# Magnetic-Charger.net
KiCad netlist of a schematic drawn in Altium Designer
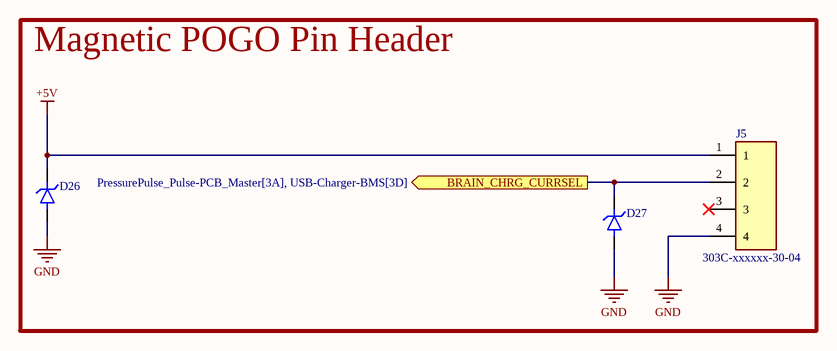
[diagram p0: Magnetic-Charger.SchDoc]

(export (version "E")
  (design (tool "Eeschema 10.0.6"))
  (components
    (comp (ref "D26")
      (value "RCLAMP0521P.TCT")
      (footprint "PressurePulse:BDFN2C051V40")
      (description "25V Clamp 4A (8/20µs) Ipp Tvs Diode Surface Mount SLP1006P2")
      (fields (field (name "MFR") "BORN"))
      (libsource (lib "PressurePulse") (part "TVS DIODE"))
    )
    (comp (ref "D27")
      (value "RCLAMP0521P.TCT")
      (footprint "PressurePulse:BDFN2C051V40")
      (description "25V Clamp 4A (8/20µs) Ipp Tvs Diode Surface Mount SLP1006P2")
      (fields (field (name "MFR") "BORN"))
      (libsource (lib "PressurePulse") (part "TVS DIODE"))
    )
    (comp (ref "J5")
      (value "303C-xxxxxx-30-04")
      (footprint "PressurePulse:MAG POGO - 4 POS MALE")
      (description "MAGNETIC POGO 4POS")
      (fields (field (name "MFR") "ATTEND Technology"))
      (libsource (lib "PressurePulse") (part "303C-xxxxxx-30-04"))
    )
  )
  (nets
    (net (code "1") (name "+5V") (class "Default")
      (node (ref "D26") (pin "K") (pinfunction "K_K") (pintype "passive"))
      (node (ref "J5") (pin "1") (pinfunction "1_1") (pintype "passive"))
    )
    (net (code "2") (name "/BRAIN_CHRG_CURRSEL") (class "Default")
      (node (ref "D27") (pin "K") (pinfunction "K_K") (pintype "passive"))
      (node (ref "J5") (pin "2") (pinfunction "2_2") (pintype "passive"))
    )
    (net (code "3") (name "GND") (class "Default")
      (node (ref "D26") (pin "A") (pinfunction "A_A") (pintype "passive"))
      (node (ref "D27") (pin "A") (pinfunction "A_A") (pintype "passive"))
      (node (ref "J5") (pin "4") (pinfunction "4_4") (pintype "passive"))
    )
    (net (code "4") (name "unconnected-(J5-Pad3)") (class "Default")
      (node (ref "J5") (pin "3") (pinfunction "3_3") (pintype "passive+no_connect"))
    )
  )
)
